# POWER.net
KiCad netlist of a schematic drawn in Altium Designer
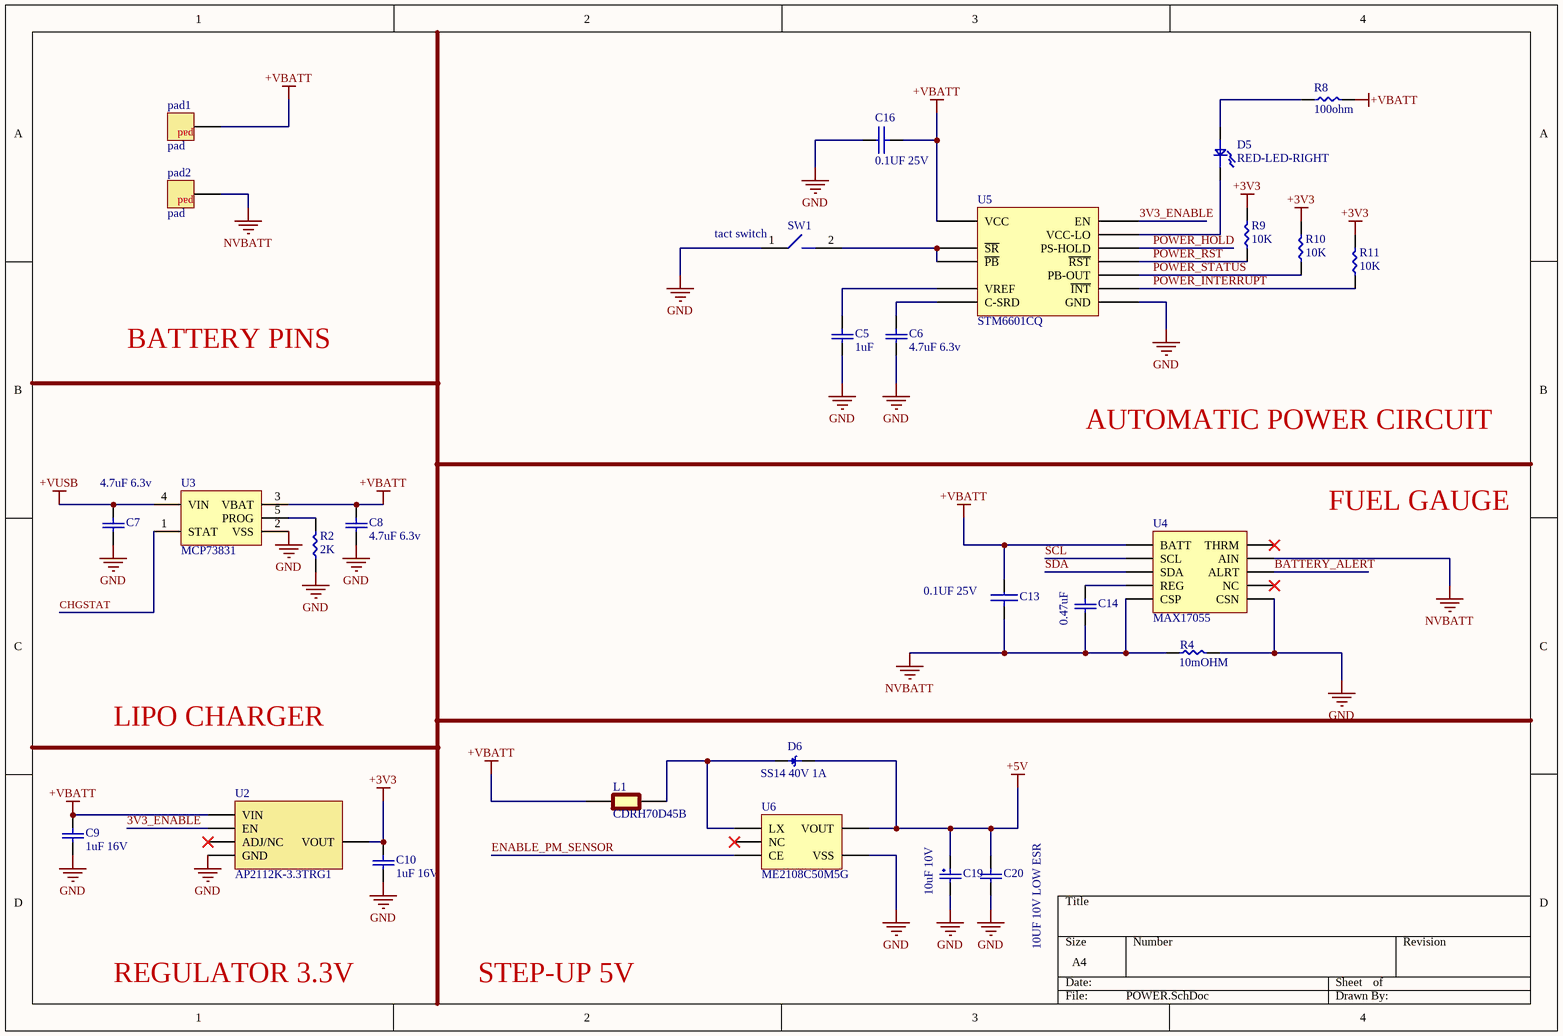
[diagram p0: POWER.SchDoc]

(export (version "E")
  (design (tool "Eeschema 10.0.6"))
  (components
    (comp (ref "C5")
      (value "1uF")
      (footprint "C0603")
      (description "CAP CER 1UF 50V X5R 0603")
      (fields
        (field (name "MANUFACTURER") "Taiyo Yuden")
        (field (name "MANUFACTURER PART NUMBER") "UMK107BJ105KA-T")
      )
      (libsource (lib "salcox") (part "UMK107BJ105KA-T"))
    )
    (comp (ref "C6")
      (value "4.7uF 6.3v")
      (footprint "C0603")
      (description "KEMET - C0603C475K9PACTU - KONDENSATOR, 4.7µF, 6.3V, 10%, X5R, 0603")
      (fields
        (field (name "MANUFACTURER") "KEMET")
        (field (name "MANUFACTURER PART NUMBER") "C0603C475K9PACTU")
      )
      (libsource (lib "salcox") (part "C0603C475K9PACTU"))
    )
    (comp (ref "C7")
      (value "4.7uF 6.3v")
      (footprint "C0603")
      (description "KEMET - C0603C475K9PACTU - KONDENSATOR, 4.7µF, 6.3V, 10%, X5R, 0603")
      (fields
        (field (name "MANUFACTURER") "KEMET")
        (field (name "MANUFACTURER PART NUMBER") "C0603C475K9PACTU")
      )
      (libsource (lib "salcox") (part "C0603C475K9PACTU"))
    )
    (comp (ref "C8")
      (value "4.7uF 6.3v")
      (footprint "C0603")
      (description "KEMET - C0603C475K9PACTU - KONDENSATOR, 4.7µF, 6.3V, 10%, X5R, 0603")
      (fields
        (field (name "MANUFACTURER") "KEMET")
        (field (name "MANUFACTURER PART NUMBER") "C0603C475K9PACTU")
      )
      (libsource (lib "salcox") (part "C0603C475K9PACTU"))
    )
    (comp (ref "C9")
      (value "1uF 16V")
      (footprint "C0805")
      (description "CAP CER 1UF 16V X7R 0805")
      (fields
        (field (name "MANUFACTURER") "Murata Electronics North America")
        (field (name "MANUFACTURER PART NUMBER") "GRM21BR71C105KA01L")
      )
      (libsource (lib "salcox") (part "GRM21BR71C105KA01L"))
    )
    (comp (ref "C10")
      (value "1uF 16V")
      (footprint "C0805")
      (description "CAP CER 1UF 16V X7R 0805")
      (fields
        (field (name "MANUFACTURER") "Murata Electronics North America")
        (field (name "MANUFACTURER PART NUMBER") "GRM21BR71C105KA01L")
      )
      (libsource (lib "salcox") (part "GRM21BR71C105KA01L"))
    )
    (comp (ref "C13")
      (value "0.1UF 25V")
      (footprint "C0603")
      (description "CAP CER 0.1UF 25V X5R 0603")
      (fields
        (field (name "MANUFACTURER") "Kyocera AVX")
        (field (name "MANUFACTURER PART NUMBER") "06033D104KAT2A")
      )
      (libsource (lib "salcoxschlib") (part "06033D104KAT2A"))
    )
    (comp (ref "C14")
      (value "0.47uF")
      (footprint "C0603")
      (description "CAP CER 0.47UF 16V 10% X5R 0603")
      (fields
        (field (name "MANUFACTURER") "KEMET")
        (field (name "MANUFACTURER PART NUMBER") "C0603C474K4PACTU")
      )
      (libsource (lib "salcoxschlib") (part "C0603C474K4PACTU"))
    )
    (comp (ref "C16")
      (value "0.1UF 25V")
      (footprint "C0603")
      (description "CAP CER 0.1UF 25V X5R 0603")
      (fields
        (field (name "MANUFACTURER") "Kyocera AVX")
        (field (name "MANUFACTURER PART NUMBER") "06033D104KAT2A")
      )
      (libsource (lib "salcoxschlib") (part "06033D104KAT2A"))
    )
    (comp (ref "C19")
      (value "10uF 10V")
      (footprint "C3216")
      (description "CAP TANT 10UF 10V 10% 1206")
      (fields
        (field (name "MANUFACTURER") "KEMET")
        (field (name "MANUFACTURER PART NUMBER") "T491A106K010AT")
      )
      (libsource (lib "salcoxschlib") (part "T491A106K010AT"))
    )
    (comp (ref "C20")
      (value "10UF 10V LOW ESR")
      (footprint "C1206")
      (description "CAP CER 10UF 10V X5R 1206")
      (fields
        (field (name "MANUFACTURER") "Taiyo Yuden")
        (field (name "MANUFACTURER PART NUMBER") "LMK316BJ106MLHT")
      )
      (libsource (lib "salcoxschlib") (part "LMK316BJ106MLHT"))
    )
    (comp (ref "D5")
      (value "RED-LED-RIGHT")
      (footprint "LED0805RIGHT")
      (description "LED RED CLEAR 0603 R/A SMD")
      (fields
        (field (name "MANUFACTURER") "Lite-On Inc.")
        (field (name "MANUFACTURER PART NUMBER") "LTST-S270KRKT")
      )
      (libsource (lib "salcox") (part "LTST-S270KRKT"))
    )
    (comp (ref "D6")
      (value "SS14 40V 1A")
      (footprint "SMA")
      (description "DIODE SCHOTTKY 40V 1A SMA")
      (fields (field (name "MANUFACTURER") "Microsemi") (field (name "MANUFACTURER PART NUMBER") "SS14"))
      (libsource (lib "salcoxschlib") (part "SS14"))
    )
    (comp (ref "L1")
      (value "CDRH70D45B")
      (footprint "CDRH70D45B")
      (description "Ind Power 47uF 20% Ferrite Drum Core")
      (fields
        (field (name "MANUFACTURER") "Sumida")
        (field (name "MANUFACTURER PART NUMBER") "CDRH70D45BT150NP-470MC")
      )
      (libsource (lib "salcox") (part "CDRH70D45BT150NP-470MC"))
    )
    (comp (ref "pad1") (value "pad") (footprint "Pad 5x4mm") (libsource (lib "salcox") (part "Pad5x4mm")))
    (comp (ref "pad2") (value "pad") (footprint "Pad 5x4mm") (libsource (lib "salcox") (part "Pad5x4mm")))
    (comp (ref "R2")
      (value "2K")
      (footprint "R0603")
      (description "RES SMD 2K OHM 1% 1/10W 0603")
      (fields
        (field (name "MANUFACTURER") "Panasonic")
        (field (name "MANUFACTURER PART NUMBER") "ERJ-3EKF2001V")
      )
      (libsource (lib "salcox") (part "ERJ-3EKF2001V"))
    )
    (comp (ref "R4")
      (value "10mOHM")
      (footprint "R2512")
      (description "RES 0.01 OHM 1% 1W 2512")
      (fields (field (name "MANUFACTURER") "Riedon") (field (name "MANUFACTURER PART NUMBER") "CSR25120R01F"))
      (libsource (lib "salcoxschlib") (part "CSR25120R01F"))
    )
    (comp (ref "R8")
      (value "100ohm")
      (footprint "R0603")
      (description "Res Thick Film 0603 100 Ohm 1% 1/10W Â±100ppm/Â°C Molded SMD SMD Paper Tape on Plastic Reel")
      (fields
        (field (name "MANUFACTURER") "Bourns")
        (field (name "MANUFACTURER PART NUMBER") "CR0603-FX-1000ELF")
      )
      (libsource (lib "salcox") (part "CR0603-FX-1000ELF"))
    )
    (comp (ref "R9")
      (value "10K")
      (footprint "R0603")
      (description "RES SMD 10K OHM 1% 1/10W 0603")
      (fields
        (field (name "MANUFACTURER") "Yageo")
        (field (name "MANUFACTURER PART NUMBER") "RC0603FR-0710KL")
      )
      (libsource (lib "salcox") (part "RC0603FR-0710KL"))
    )
    (comp (ref "R10")
      (value "10K")
      (footprint "R0603")
      (description "RES SMD 10K OHM 1% 1/10W 0603")
      (fields
        (field (name "MANUFACTURER") "Yageo")
        (field (name "MANUFACTURER PART NUMBER") "RC0603FR-0710KL")
      )
      (libsource (lib "salcox") (part "RC0603FR-0710KL"))
    )
    (comp (ref "R11")
      (value "10K")
      (footprint "R0603")
      (description "RES SMD 10K OHM 1% 1/10W 0603")
      (fields
        (field (name "MANUFACTURER") "Yageo")
        (field (name "MANUFACTURER PART NUMBER") "RC0603FR-0710KL")
      )
      (libsource (lib "salcox") (part "RC0603FR-0710KL"))
    )
    (comp (ref "SW1")
      (value "tact switch")
      (footprint "Tacticle smd")
      (description "SWITCH TACTILE SPST-NO 0.05A 12V")
      (fields
        (field (name "MANUFACTURER") "Panasonic Electronic Components")
        (field (name "MANUFACTURER PART NUMBER") "EVQ-P7A01P")
      )
      (libsource (lib "salcox") (part "EVQ-P7A01P"))
    )
    (comp (ref "U2")
      (value "AP2112K-3.3TRG1")
      (footprint "SOT-23-5")
      (description "IC REG LINEAR 3.3V 600MA SOT25")
      (fields (field (name "MANUFACTURER") "Diodes Incorporated"))
      (libsource (lib "salcox") (part "AP2112K-3.3TRG1"))
    )
    (comp (ref "U3")
      (value "MCP73831")
      (footprint "SOT-23-5")
      (description "IC CONTROLLR LI-ION 4.2V SOT23-5")
      (fields
        (field (name "MANUFACTURER") "Microchip Technology")
        (field (name "MANUFACTURER PART NUMBER") "MCP73831T-2ACI/OT")
      )
      (libsource (lib "salcox") (part "MCP73831T-2ACI/OT"))
    )
    (comp (ref "U4")
      (value "MAX17055")
      (footprint "TDFN-EP")
      (description "IC FUEL GAUGE MODELGAUGE 10TDFN")
      (fields (field (name "MANUFACTURER") "Maxim") (field (name "MANUFACTURER PART NUMBER") "MAX17055ETB+T"))
      (libsource (lib "salcoxschlib") (part "MAX17055ETB+T"))
    )
    (comp (ref "U5")
      (value "STM6601CQ")
      (footprint "SON50P300X200X80-12N")
      (description "On/Off Controller 12-Pin TDFN T/R")
      (fields
        (field (name "MANUFACTURER") "STMicroelectronics")
        (field (name "MANUFACTURER PART NUMBER") "STM6601CQ2BDM6F")
      )
      (libsource (lib "salcox") (part "STM6601CQ2BDM6F"))
    )
    (comp (ref "U6")
      (value "ME2108C50M5G")
      (footprint "SOT-23-5")
      (libsource (lib "salcoxschlib") (part "ME2108C50M5G"))
    )
  )
  (nets
    (net (code "1") (name "+3V3") (class "Default")
      (node (ref "C10") (pin "2") (pinfunction "2_2") (pintype "passive"))
      (node (ref "R10") (pin "2") (pinfunction "2_2") (pintype "passive"))
      (node (ref "R11") (pin "2") (pinfunction "2_2") (pintype "passive"))
      (node (ref "R9") (pin "2") (pinfunction "2_2") (pintype "passive"))
      (node (ref "U2") (pin "5") (pinfunction "VOUT_5") (pintype "passive"))
    )
    (net (code "2") (name "+5V") (class "Default")
      (node (ref "C19") (pin "2") (pinfunction "2_2") (pintype "passive"))
      (node (ref "C20") (pin "2") (pinfunction "2_2") (pintype "passive"))
      (node (ref "D6") (pin "2") (pinfunction "2_2") (pintype "passive"))
      (node (ref "U6") (pin "2") (pinfunction "VOUT_2") (pintype "passive"))
    )
    (net (code "3") (name "+VBATT") (class "Default")
      (node (ref "C13") (pin "1") (pinfunction "1_1") (pintype "passive"))
      (node (ref "C16") (pin "2") (pinfunction "2_2") (pintype "passive"))
      (node (ref "C8") (pin "2") (pinfunction "2_2") (pintype "passive"))
      (node (ref "C9") (pin "2") (pinfunction "2_2") (pintype "passive"))
      (node (ref "L1") (pin "1") (pinfunction "1_1") (pintype "passive"))
      (node (ref "R8") (pin "2") (pinfunction "2_2") (pintype "passive"))
      (node (ref "U2") (pin "1") (pinfunction "VIN_1") (pintype "passive"))
      (node (ref "U3") (pin "3") (pinfunction "VBAT_3") (pintype "passive"))
      (node (ref "U4") (pin "10") (pinfunction "BATT_10") (pintype "passive"))
      (node (ref "U5") (pin "1") (pinfunction "VCC_1") (pintype "passive"))
      (node (ref "pad1") (pin "1") (pinfunction "1_1") (pintype "passive"))
    )
    (net (code "4") (name "+VUSB") (class "Default")
      (node (ref "C7") (pin "2") (pinfunction "2_2") (pintype "passive"))
      (node (ref "U3") (pin "4") (pinfunction "VIN_4") (pintype "passive"))
    )
    (net (code "5") (name "/3V3_ENABLE") (class "Default")
      (node (ref "U2") (pin "3") (pinfunction "EN_3") (pintype "passive"))
      (node (ref "U5") (pin "9") (pinfunction "EN_9") (pintype "passive"))
    )
    (net (code "6") (name "/BATTERY_ALERT") (class "Default")
      (node (ref "U4") (pin "8") (pinfunction "ALRT_8") (pintype "passive"))
    )
    (net (code "7") (name "/CHGSTAT") (class "Default")
      (node (ref "U3") (pin "1") (pinfunction "STAT_1") (pintype "passive"))
    )
    (net (code "8") (name "/ENABLE_PM_SENSOR") (class "Default")
      (node (ref "U6") (pin "1") (pinfunction "CE_1") (pintype "passive"))
    )
    (net (code "9") (name "/POWER_HOLD") (class "Default")
      (node (ref "U5") (pin "4") (pinfunction "PS-HOLD_4") (pintype "passive"))
    )
    (net (code "10") (name "/POWER_INTERRUPT") (class "Default")
      (node (ref "R11") (pin "1") (pinfunction "1_1") (pintype "passive"))
      (node (ref "U5") (pin "11") (pinfunction "~{INT}_11") (pintype "passive"))
    )
    (net (code "11") (name "/POWER_RST") (class "Default")
      (node (ref "R9") (pin "1") (pinfunction "1_1") (pintype "passive"))
      (node (ref "U5") (pin "10") (pinfunction "~{RST}_10") (pintype "passive"))
    )
    (net (code "12") (name "/POWER_STATUS") (class "Default")
      (node (ref "R10") (pin "1") (pinfunction "1_1") (pintype "passive"))
      (node (ref "U5") (pin "8") (pinfunction "PB-OUT_8") (pintype "passive"))
    )
    (net (code "13") (name "/SCL") (class "Default")
      (node (ref "U4") (pin "3") (pinfunction "SCL_3") (pintype "passive"))
    )
    (net (code "14") (name "/SDA") (class "Default")
      (node (ref "U4") (pin "4") (pinfunction "SDA_4") (pintype "passive"))
    )
    (net (code "15") (name "GND") (class "Default")
      (node (ref "C10") (pin "1") (pinfunction "1_1") (pintype "passive"))
      (node (ref "C16") (pin "1") (pinfunction "1_1") (pintype "passive"))
      (node (ref "C19") (pin "1") (pinfunction "1_1") (pintype "passive"))
      (node (ref "C20") (pin "1") (pinfunction "1_1") (pintype "passive"))
      (node (ref "C5") (pin "1") (pinfunction "1_1") (pintype "passive"))
      (node (ref "C6") (pin "1") (pinfunction "1_1") (pintype "passive"))
      (node (ref "C7") (pin "1") (pinfunction "1_1") (pintype "passive"))
      (node (ref "C8") (pin "1") (pinfunction "1_1") (pintype "passive"))
      (node (ref "C9") (pin "1") (pinfunction "1_1") (pintype "passive"))
      (node (ref "R2") (pin "1") (pinfunction "1_1") (pintype "passive"))
      (node (ref "R4") (pin "2") (pinfunction "2_2") (pintype "passive"))
      (node (ref "SW1") (pin "1") (pintype "passive"))
      (node (ref "U2") (pin "2") (pinfunction "GND_2") (pintype "passive"))
      (node (ref "U3") (pin "2") (pinfunction "VSS_2") (pintype "passive"))
      (node (ref "U4") (pin "5") (pinfunction "CSN_5") (pintype "passive"))
      (node (ref "U5") (pin "12") (pinfunction "GND_12") (pintype "passive"))
      (node (ref "U6") (pin "4") (pinfunction "VSS_4") (pintype "passive"))
    )
    (net (code "16") (name "NVBATT") (class "Default")
      (node (ref "C13") (pin "2") (pinfunction "2_2") (pintype "passive"))
      (node (ref "C14") (pin "1") (pinfunction "1_1") (pintype "passive"))
      (node (ref "R4") (pin "1") (pinfunction "1_1") (pintype "passive"))
      (node (ref "U4") (pin "2") (pinfunction "AIN_2") (pintype "passive"))
      (node (ref "U4") (pin "6") (pinfunction "CSP_6") (pintype "passive"))
      (node (ref "pad2") (pin "1") (pinfunction "1_1") (pintype "passive"))
    )
    (net (code "17") (name "Net-(D5-Pad1)") (class "Default")
      (node (ref "D5") (pin "1") (pinfunction "1_1") (pintype "passive"))
      (node (ref "R8") (pin "1") (pinfunction "1_1") (pintype "passive"))
    )
    (net (code "18") (name "Net-(U3-PROG)") (class "Default")
      (node (ref "R2") (pin "2") (pinfunction "2_2") (pintype "passive"))
      (node (ref "U3") (pin "5") (pinfunction "PROG_5") (pintype "passive"))
    )
    (net (code "19") (name "Net-(U4-REG)") (class "Default")
      (node (ref "C14") (pin "2") (pinfunction "2_2") (pintype "passive"))
      (node (ref "U4") (pin "7") (pinfunction "REG_7") (pintype "passive"))
    )
    (net (code "20") (name "Net-(U5-C-SRD)") (class "Default")
      (node (ref "C6") (pin "2") (pinfunction "2_2") (pintype "passive"))
      (node (ref "U5") (pin "5") (pinfunction "C-SRD_5") (pintype "passive"))
    )
    (net (code "21") (name "Net-(U5-VCC-LO)") (class "Default")
      (node (ref "D5") (pin "2") (pinfunction "2_2") (pintype "passive"))
      (node (ref "U5") (pin "7") (pinfunction "VCC-LO_7") (pintype "passive"))
    )
    (net (code "22") (name "Net-(U5-VREF)") (class "Default")
      (node (ref "C5") (pin "2") (pinfunction "2_2") (pintype "passive"))
      (node (ref "U5") (pin "3") (pinfunction "VREF_3") (pintype "passive"))
    )
    (net (code "23") (name "Net-(U5-~{PB})") (class "Default")
      (node (ref "SW1") (pin "2") (pintype "passive"))
      (node (ref "U5") (pin "2") (pinfunction "~{SR}_2") (pintype "passive"))
      (node (ref "U5") (pin "6") (pinfunction "~{PB}_6") (pintype "passive"))
    )
    (net (code "24") (name "Net-(U6-LX)") (class "Default")
      (node (ref "D6") (pin "1") (pinfunction "1_1") (pintype "passive"))
      (node (ref "L1") (pin "2") (pinfunction "2_2") (pintype "passive"))
      (node (ref "U6") (pin "5") (pinfunction "LX_5") (pintype "passive"))
    )
    (net (code "25") (name "unconnected-(U2-ADJ{slash}NC-Pad4)") (class "Default")
      (node (ref "U2") (pin "4") (pinfunction "ADJ/NC_4") (pintype "passive+no_connect"))
    )
    (net (code "26") (name "unconnected-(U4-NC-Pad1)") (class "Default")
      (node (ref "U4") (pin "1") (pinfunction "NC_1") (pintype "passive+no_connect"))
    )
    (net (code "27") (name "unconnected-(U4-THRM-Pad9)") (class "Default")
      (node (ref "U4") (pin "9") (pinfunction "THRM_9") (pintype "passive+no_connect"))
    )
    (net (code "28") (name "unconnected-(U6-NC-Pad3)") (class "Default")
      (node (ref "U6") (pin "3") (pinfunction "NC_3") (pintype "passive+no_connect"))
    )
  )
)
